# Display_Unit.net
KiCad netlist of a schematic drawn in Altium Designer
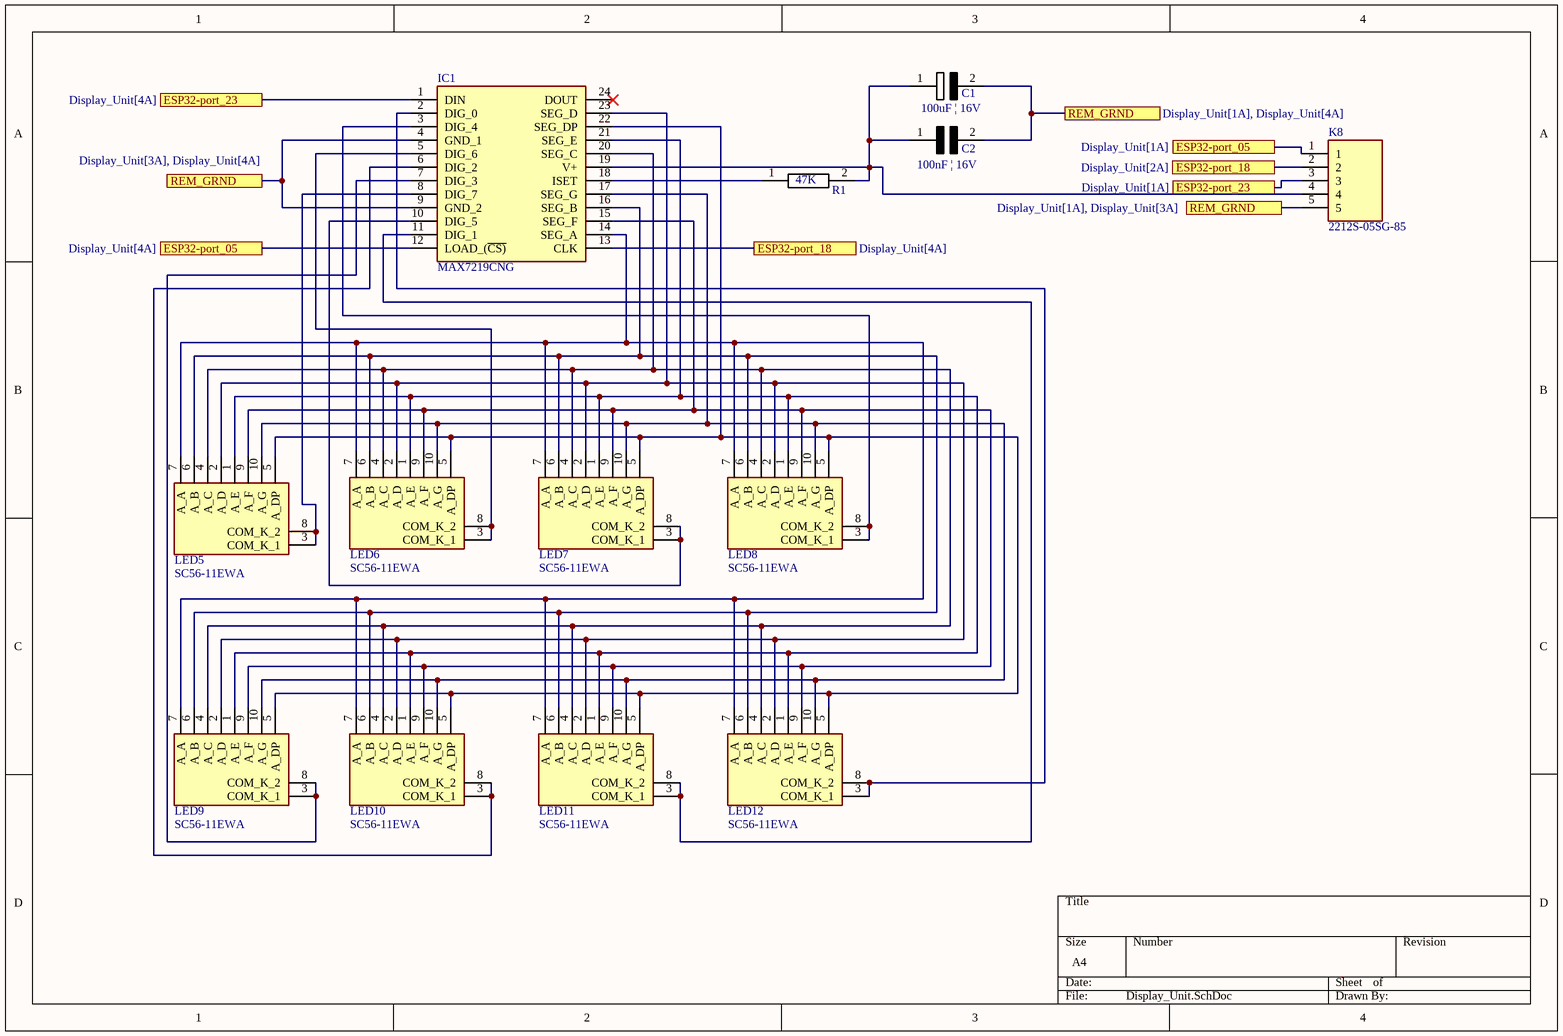
[diagram p0: Display_Unit.SchDoc]

(export (version "E")
  (design (tool "Eeschema 10.0.6"))
  (components
    (comp (ref "C1")
      (value "100uF ¦ 16V")
      (footprint "C0805")
      (description "0805 ceramic capacitor")
      (fields
        (field (name "MANUFACTURER_PART_NUMBER") "GRM188R71H103KA01D")
        (field (name "MOUSER PART NUMBER") "81-GRM39X103K50D")
      )
      (libsource (lib "Schlib1") (part "elektrolytischeC0805"))
    )
    (comp (ref "C2")
      (value "100nF ¦ 16V")
      (footprint "C0805")
      (description "0805 ceramic capacitor")
      (fields
        (field (name "MANUFACTURER_PART_NUMBER") "GRM188R71H103KA01D")
        (field (name "MOUSER PART NUMBER") "81-GRM39X103K50D")
      )
      (libsource (lib "Schlib1") (part "KeramischeC0805_1"))
    )
    (comp (ref "IC1")
      (value "MAX7219CNG")
      (footprint "SamacSys:DIP794W56P254L3054H457Q24N")
      (description "Integrated Circuit")
      (fields (field (name "MOUSER PART NUMBER") "700-MAX7219CNG-NR"))
      (libsource (lib "Schlib1") (part "MAX7219CNG"))
    )
    (comp (ref "K8")
      (value "2212S-05SG-85")
      (footprint "SamacSys:RHDR5W74P0X254_1X5_1320X250X850P")
      (description "Connector")
      (libsource (lib "Schlib1") (part "2212S-05SG-85"))
    )
    (comp (ref "LED5")
      (value "SC56-11EWA")
      (footprint "SamacSys:DIPS1524W75P254L1270H825Q10N")
      (description "Display")
      (fields (field (name "MOUSER PART NUMBER") "604-SC56-11EWA"))
      (libsource (lib "Schlib1") (part "SC56-11EWA"))
    )
    (comp (ref "LED6")
      (value "SC56-11EWA")
      (footprint "SamacSys:DIPS1524W75P254L1270H825Q10N")
      (description "Display")
      (fields (field (name "MOUSER PART NUMBER") "604-SC56-11EWA"))
      (libsource (lib "Schlib1") (part "SC56-11EWA"))
    )
    (comp (ref "LED7")
      (value "SC56-11EWA")
      (footprint "SamacSys:DIPS1524W75P254L1270H825Q10N")
      (description "Display")
      (fields (field (name "MOUSER PART NUMBER") "604-SC56-11EWA"))
      (libsource (lib "Schlib1") (part "SC56-11EWA"))
    )
    (comp (ref "LED8")
      (value "SC56-11EWA")
      (footprint "SamacSys:DIPS1524W75P254L1270H825Q10N")
      (description "Display")
      (fields (field (name "MOUSER PART NUMBER") "604-SC56-11EWA"))
      (libsource (lib "Schlib1") (part "SC56-11EWA"))
    )
    (comp (ref "LED9")
      (value "SC56-11EWA")
      (footprint "SamacSys:DIPS1524W75P254L1270H825Q10N")
      (description "Display")
      (fields (field (name "MOUSER PART NUMBER") "604-SC56-11EWA"))
      (libsource (lib "Schlib1") (part "SC56-11EWA"))
    )
    (comp (ref "LED10")
      (value "SC56-11EWA")
      (footprint "SamacSys:DIPS1524W75P254L1270H825Q10N")
      (description "Display")
      (fields (field (name "MOUSER PART NUMBER") "604-SC56-11EWA"))
      (libsource (lib "Schlib1") (part "SC56-11EWA"))
    )
    (comp (ref "LED11")
      (value "SC56-11EWA")
      (footprint "SamacSys:DIPS1524W75P254L1270H825Q10N")
      (description "Display")
      (fields (field (name "MOUSER PART NUMBER") "604-SC56-11EWA"))
      (libsource (lib "Schlib1") (part "SC56-11EWA"))
    )
    (comp (ref "LED12")
      (value "SC56-11EWA")
      (footprint "SamacSys:DIPS1524W75P254L1270H825Q10N")
      (description "Display")
      (fields (field (name "MOUSER PART NUMBER") "604-SC56-11EWA"))
      (libsource (lib "Schlib1") (part "SC56-11EWA"))
    )
    (comp (ref "R1")
      (value "47K")
      (footprint "C0805")
      (description "Resistor0805")
      (fields
        (field (name "MANUFACTURER_PART_NUMBER") "CRCW08050000Z0EAHP")
        (field (name "MOUSER PART NUMBER") "71-CRCW08050000Z0EAH")
      )
      (libsource (lib "Schlib1") (part "Resistor0805"))
    )
  )
  (nets
    (net (code "1") (name "/ESP32-port_05") (class "Default")
      (node (ref "IC1") (pin "12") (pinfunction "LOAD_(~{CS)}_12") (pintype "passive"))
      (node (ref "K8") (pin "1") (pinfunction "1_1") (pintype "passive"))
    )
    (net (code "2") (name "/ESP32-port_18") (class "Default")
      (node (ref "IC1") (pin "13") (pinfunction "CLK_13") (pintype "passive"))
      (node (ref "K8") (pin "2") (pinfunction "2_2") (pintype "passive"))
    )
    (net (code "3") (name "/ESP32-port_23") (class "Default")
      (node (ref "IC1") (pin "1") (pinfunction "DIN_1") (pintype "passive"))
      (node (ref "K8") (pin "3") (pinfunction "3_3") (pintype "passive"))
    )
    (net (code "4") (name "/REM_GRND") (class "Default")
      (node (ref "C1") (pin "2") (pinfunction "2_2") (pintype "passive"))
      (node (ref "C2") (pin "2") (pinfunction "2_2") (pintype "passive"))
      (node (ref "IC1") (pin "4") (pinfunction "GND_1_4") (pintype "passive"))
      (node (ref "IC1") (pin "9") (pinfunction "GND_2_9") (pintype "passive"))
      (node (ref "K8") (pin "5") (pinfunction "5_5") (pintype "passive"))
    )
    (net (code "5") (name "Net-(IC1-DIG_0)") (class "Default")
      (node (ref "IC1") (pin "2") (pinfunction "DIG_0_2") (pintype "passive"))
      (node (ref "LED12") (pin "3") (pinfunction "COM_K_1_3") (pintype "passive"))
      (node (ref "LED12") (pin "8") (pinfunction "COM_K_2_8") (pintype "passive"))
    )
    (net (code "6") (name "Net-(IC1-DIG_1)") (class "Default")
      (node (ref "IC1") (pin "11") (pinfunction "DIG_1_11") (pintype "passive"))
      (node (ref "LED11") (pin "3") (pinfunction "COM_K_1_3") (pintype "passive"))
      (node (ref "LED11") (pin "8") (pinfunction "COM_K_2_8") (pintype "passive"))
    )
    (net (code "7") (name "Net-(IC1-DIG_2)") (class "Default")
      (node (ref "IC1") (pin "6") (pinfunction "DIG_2_6") (pintype "passive"))
      (node (ref "LED10") (pin "3") (pinfunction "COM_K_1_3") (pintype "passive"))
      (node (ref "LED10") (pin "8") (pinfunction "COM_K_2_8") (pintype "passive"))
    )
    (net (code "8") (name "Net-(IC1-DIG_3)") (class "Default")
      (node (ref "IC1") (pin "7") (pinfunction "DIG_3_7") (pintype "passive"))
      (node (ref "LED9") (pin "3") (pinfunction "COM_K_1_3") (pintype "passive"))
      (node (ref "LED9") (pin "8") (pinfunction "COM_K_2_8") (pintype "passive"))
    )
    (net (code "9") (name "Net-(IC1-DIG_4)") (class "Default")
      (node (ref "IC1") (pin "3") (pinfunction "DIG_4_3") (pintype "passive"))
      (node (ref "LED8") (pin "3") (pinfunction "COM_K_1_3") (pintype "passive"))
      (node (ref "LED8") (pin "8") (pinfunction "COM_K_2_8") (pintype "passive"))
    )
    (net (code "10") (name "Net-(IC1-DIG_5)") (class "Default")
      (node (ref "IC1") (pin "10") (pinfunction "DIG_5_10") (pintype "passive"))
      (node (ref "LED7") (pin "3") (pinfunction "COM_K_1_3") (pintype "passive"))
      (node (ref "LED7") (pin "8") (pinfunction "COM_K_2_8") (pintype "passive"))
    )
    (net (code "11") (name "Net-(IC1-DIG_6)") (class "Default")
      (node (ref "IC1") (pin "5") (pinfunction "DIG_6_5") (pintype "passive"))
      (node (ref "LED6") (pin "3") (pinfunction "COM_K_1_3") (pintype "passive"))
      (node (ref "LED6") (pin "8") (pinfunction "COM_K_2_8") (pintype "passive"))
    )
    (net (code "12") (name "Net-(IC1-DIG_7)") (class "Default")
      (node (ref "IC1") (pin "8") (pinfunction "DIG_7_8") (pintype "passive"))
      (node (ref "LED5") (pin "3") (pinfunction "COM_K_1_3") (pintype "passive"))
      (node (ref "LED5") (pin "8") (pinfunction "COM_K_2_8") (pintype "passive"))
    )
    (net (code "13") (name "Net-(IC1-ISET)") (class "Default")
      (node (ref "IC1") (pin "18") (pinfunction "ISET_18") (pintype "passive"))
      (node (ref "R1") (pin "1") (pinfunction "1_1") (pintype "passive"))
    )
    (net (code "14") (name "Net-(IC1-SEG_A)") (class "Default")
      (node (ref "IC1") (pin "14") (pinfunction "SEG_A_14") (pintype "passive"))
      (node (ref "LED10") (pin "7") (pinfunction "A_A_7") (pintype "passive"))
      (node (ref "LED11") (pin "7") (pinfunction "A_A_7") (pintype "passive"))
      (node (ref "LED12") (pin "7") (pinfunction "A_A_7") (pintype "passive"))
      (node (ref "LED5") (pin "7") (pinfunction "A_A_7") (pintype "passive"))
      (node (ref "LED6") (pin "7") (pinfunction "A_A_7") (pintype "passive"))
      (node (ref "LED7") (pin "7") (pinfunction "A_A_7") (pintype "passive"))
      (node (ref "LED8") (pin "7") (pinfunction "A_A_7") (pintype "passive"))
      (node (ref "LED9") (pin "7") (pinfunction "A_A_7") (pintype "passive"))
    )
    (net (code "15") (name "Net-(IC1-SEG_B)") (class "Default")
      (node (ref "IC1") (pin "16") (pinfunction "SEG_B_16") (pintype "passive"))
      (node (ref "LED10") (pin "6") (pinfunction "A_B_6") (pintype "passive"))
      (node (ref "LED11") (pin "6") (pinfunction "A_B_6") (pintype "passive"))
      (node (ref "LED12") (pin "6") (pinfunction "A_B_6") (pintype "passive"))
      (node (ref "LED5") (pin "6") (pinfunction "A_B_6") (pintype "passive"))
      (node (ref "LED6") (pin "6") (pinfunction "A_B_6") (pintype "passive"))
      (node (ref "LED7") (pin "6") (pinfunction "A_B_6") (pintype "passive"))
      (node (ref "LED8") (pin "6") (pinfunction "A_B_6") (pintype "passive"))
      (node (ref "LED9") (pin "6") (pinfunction "A_B_6") (pintype "passive"))
    )
    (net (code "16") (name "Net-(IC1-SEG_C)") (class "Default")
      (node (ref "IC1") (pin "20") (pinfunction "SEG_C_20") (pintype "passive"))
      (node (ref "LED10") (pin "4") (pinfunction "A_C_4") (pintype "passive"))
      (node (ref "LED11") (pin "4") (pinfunction "A_C_4") (pintype "passive"))
      (node (ref "LED12") (pin "4") (pinfunction "A_C_4") (pintype "passive"))
      (node (ref "LED5") (pin "4") (pinfunction "A_C_4") (pintype "passive"))
      (node (ref "LED6") (pin "4") (pinfunction "A_C_4") (pintype "passive"))
      (node (ref "LED7") (pin "4") (pinfunction "A_C_4") (pintype "passive"))
      (node (ref "LED8") (pin "4") (pinfunction "A_C_4") (pintype "passive"))
      (node (ref "LED9") (pin "4") (pinfunction "A_C_4") (pintype "passive"))
    )
    (net (code "17") (name "Net-(IC1-SEG_D)") (class "Default")
      (node (ref "IC1") (pin "23") (pinfunction "SEG_D_23") (pintype "passive"))
      (node (ref "LED10") (pin "2") (pinfunction "A_D_2") (pintype "passive"))
      (node (ref "LED11") (pin "2") (pinfunction "A_D_2") (pintype "passive"))
      (node (ref "LED12") (pin "2") (pinfunction "A_D_2") (pintype "passive"))
      (node (ref "LED5") (pin "2") (pinfunction "A_D_2") (pintype "passive"))
      (node (ref "LED6") (pin "2") (pinfunction "A_D_2") (pintype "passive"))
      (node (ref "LED7") (pin "2") (pinfunction "A_D_2") (pintype "passive"))
      (node (ref "LED8") (pin "2") (pinfunction "A_D_2") (pintype "passive"))
      (node (ref "LED9") (pin "2") (pinfunction "A_D_2") (pintype "passive"))
    )
    (net (code "18") (name "Net-(IC1-SEG_DP)") (class "Default")
      (node (ref "IC1") (pin "22") (pinfunction "SEG_DP_22") (pintype "passive"))
      (node (ref "LED10") (pin "5") (pinfunction "A_DP_5") (pintype "passive"))
      (node (ref "LED11") (pin "5") (pinfunction "A_DP_5") (pintype "passive"))
      (node (ref "LED12") (pin "5") (pinfunction "A_DP_5") (pintype "passive"))
      (node (ref "LED5") (pin "5") (pinfunction "A_DP_5") (pintype "passive"))
      (node (ref "LED6") (pin "5") (pinfunction "A_DP_5") (pintype "passive"))
      (node (ref "LED7") (pin "5") (pinfunction "A_DP_5") (pintype "passive"))
      (node (ref "LED8") (pin "5") (pinfunction "A_DP_5") (pintype "passive"))
      (node (ref "LED9") (pin "5") (pinfunction "A_DP_5") (pintype "passive"))
    )
    (net (code "19") (name "Net-(IC1-SEG_E)") (class "Default")
      (node (ref "IC1") (pin "21") (pinfunction "SEG_E_21") (pintype "passive"))
      (node (ref "LED10") (pin "1") (pinfunction "A_E_1") (pintype "passive"))
      (node (ref "LED11") (pin "1") (pinfunction "A_E_1") (pintype "passive"))
      (node (ref "LED12") (pin "1") (pinfunction "A_E_1") (pintype "passive"))
      (node (ref "LED5") (pin "1") (pinfunction "A_E_1") (pintype "passive"))
      (node (ref "LED6") (pin "1") (pinfunction "A_E_1") (pintype "passive"))
      (node (ref "LED7") (pin "1") (pinfunction "A_E_1") (pintype "passive"))
      (node (ref "LED8") (pin "1") (pinfunction "A_E_1") (pintype "passive"))
      (node (ref "LED9") (pin "1") (pinfunction "A_E_1") (pintype "passive"))
    )
    (net (code "20") (name "Net-(IC1-SEG_F)") (class "Default")
      (node (ref "IC1") (pin "15") (pinfunction "SEG_F_15") (pintype "passive"))
      (node (ref "LED10") (pin "9") (pinfunction "A_F_9") (pintype "passive"))
      (node (ref "LED11") (pin "9") (pinfunction "A_F_9") (pintype "passive"))
      (node (ref "LED12") (pin "9") (pinfunction "A_F_9") (pintype "passive"))
      (node (ref "LED5") (pin "9") (pinfunction "A_F_9") (pintype "passive"))
      (node (ref "LED6") (pin "9") (pinfunction "A_F_9") (pintype "passive"))
      (node (ref "LED7") (pin "9") (pinfunction "A_F_9") (pintype "passive"))
      (node (ref "LED8") (pin "9") (pinfunction "A_F_9") (pintype "passive"))
      (node (ref "LED9") (pin "9") (pinfunction "A_F_9") (pintype "passive"))
    )
    (net (code "21") (name "Net-(IC1-SEG_G)") (class "Default")
      (node (ref "IC1") (pin "17") (pinfunction "SEG_G_17") (pintype "passive"))
      (node (ref "LED10") (pin "10") (pinfunction "A_G_10") (pintype "passive"))
      (node (ref "LED11") (pin "10") (pinfunction "A_G_10") (pintype "passive"))
      (node (ref "LED12") (pin "10") (pinfunction "A_G_10") (pintype "passive"))
      (node (ref "LED5") (pin "10") (pinfunction "A_G_10") (pintype "passive"))
      (node (ref "LED6") (pin "10") (pinfunction "A_G_10") (pintype "passive"))
      (node (ref "LED7") (pin "10") (pinfunction "A_G_10") (pintype "passive"))
      (node (ref "LED8") (pin "10") (pinfunction "A_G_10") (pintype "passive"))
      (node (ref "LED9") (pin "10") (pinfunction "A_G_10") (pintype "passive"))
    )
    (net (code "22") (name "Net-(IC1-V+)") (class "Default")
      (node (ref "C1") (pin "1") (pinfunction "1_1") (pintype "passive"))
      (node (ref "C2") (pin "1") (pinfunction "1_1") (pintype "passive"))
      (node (ref "IC1") (pin "19") (pinfunction "V+_19") (pintype "passive"))
      (node (ref "K8") (pin "4") (pinfunction "4_4") (pintype "passive"))
      (node (ref "R1") (pin "2") (pinfunction "2_2") (pintype "passive"))
    )
    (net (code "23") (name "unconnected-(IC1-DOUT-Pad24)") (class "Default")
      (node (ref "IC1") (pin "24") (pinfunction "DOUT_24") (pintype "passive+no_connect"))
    )
  )
)
